# Connectors_2.net
KiCad netlist of a schematic drawn in Altium Designer
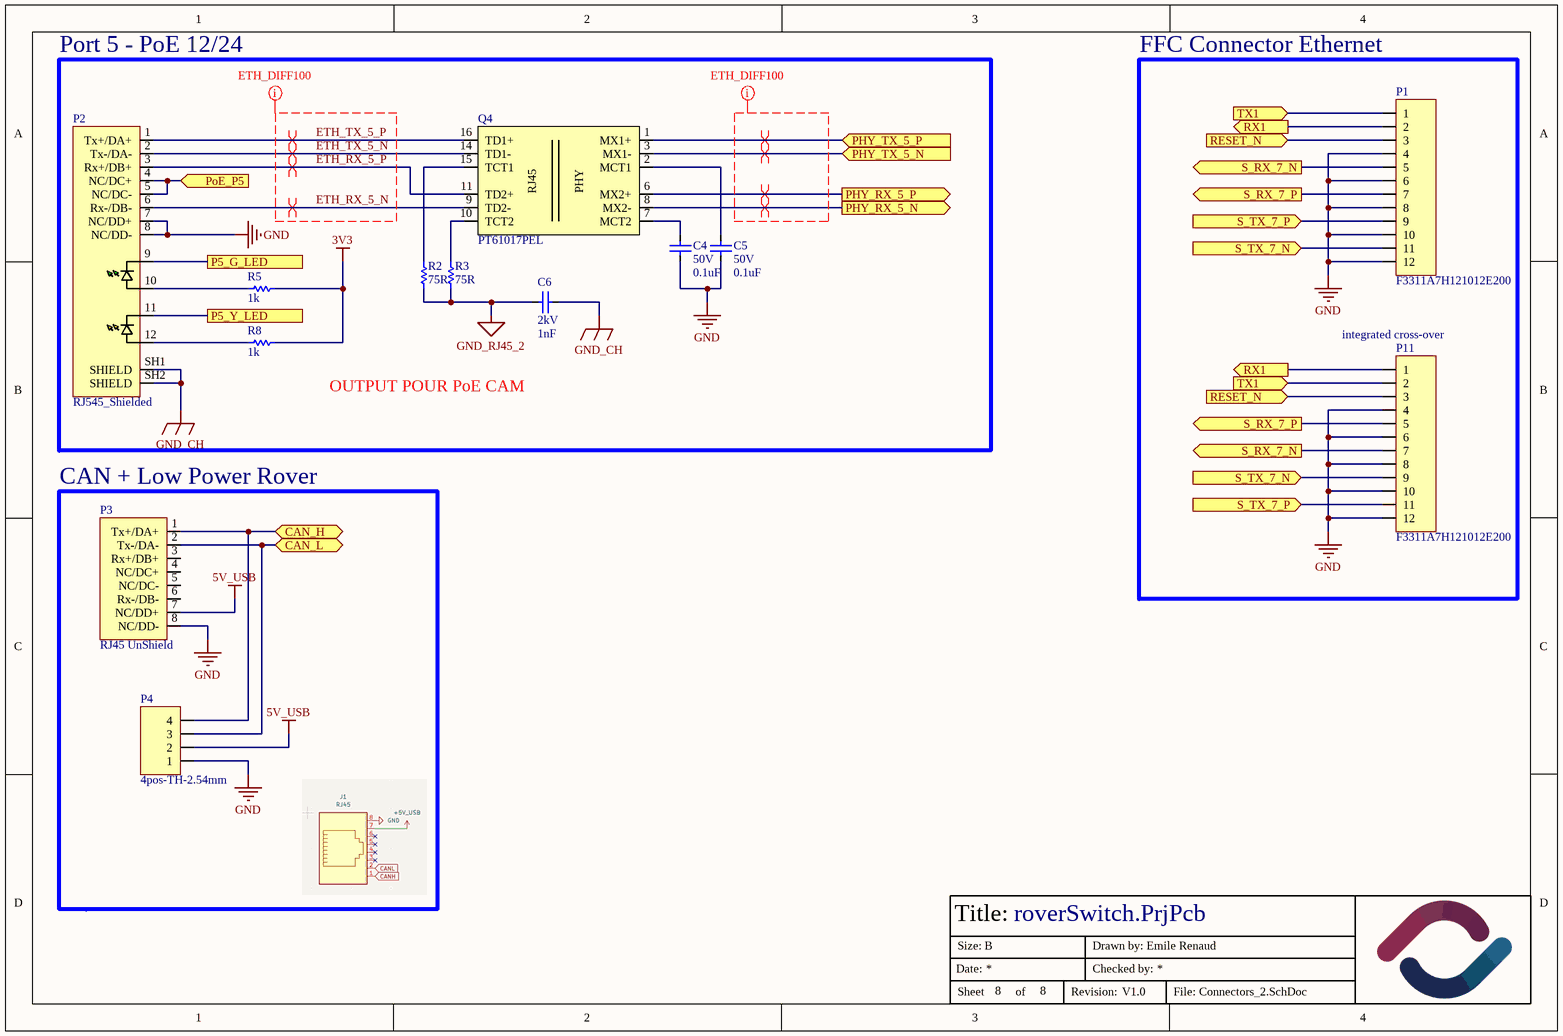
[diagram p0: Connectors_2.SchDoc]

(export (version "E")
  (design (tool "Eeschema 10.0.6"))
  (components
    (comp (ref "C4")
      (value "0.1uF")
      (footprint "CAPACITOR-0603")
      (description "Capacitor-0603-0.1uF-50V-X7R")
      (fields (field (name "VOLT") "50V"))
      (libsource (lib "Capacitors") (part "Capacitor-0603-0.1uF-50V-X7R"))
    )
    (comp (ref "C5")
      (value "0.1uF")
      (footprint "CAPACITOR-0603")
      (description "Capacitor-0603-0.1uF-50V-X7R")
      (fields (field (name "VOLT") "50V"))
      (libsource (lib "Capacitors") (part "Capacitor-0603-0.1uF-50V-X7R"))
    )
    (comp (ref "C6")
      (value "1nF")
      (footprint "CAPACITOR-1206")
      (description "Capacitor-1206-1nF-2kV-X7R")
      (fields (field (name "VOLT") "2kV"))
      (libsource (lib "Capacitors") (part "Capacitor-1206-1nF-2kV-X7R"))
    )
    (comp (ref "P1")
      (value "F3311A7H121012E200")
      (footprint "AMPHENOL_F3311A7H121012E200")
      (description "CONN FFC FPC 12POS 0.5MM R/A")
      (libsource (lib "FFC_connector") (part "FFC-12P-0.5MM-R/A"))
    )
    (comp (ref "P2")
      (value "RJ545_Shielded")
      (footprint "ADAMTECH_MTJ-88ARX1-FSM-LG")
      (description "Jack Modular Connector 8p8c (RJ45, Ethernet) 90° Angle (Right) Shielded with LEDs")
      (libsource (lib "PC-connector") (part "RJ545_Shielded"))
    )
    (comp (ref "P3")
      (value "RJ45 UnShield")
      (footprint "AMPHENOL_54602-908LF")
      (description "Jack Modular Connector 8p8c (RJ45, Ethernet) 90° Angle (Right) Unshielded Cat3")
      (libsource (lib "PC-connector") (part "RJ545"))
    )
    (comp (ref "P4")
      (value "4pos-TH-2.54mm")
      (footprint "HDR1X4")
      (description "4pos TH 2.54mm Header")
      (libsource (lib "Header") (part "4pos-TH-2.54mm"))
    )
    (comp (ref "P11")
      (value "F3311A7H121012E200")
      (footprint "AMPHENOL_F3311A7H121012E200")
      (description "CONN FFC FPC 12POS 0.5MM R/A")
      (libsource (lib "FFC_connector") (part "FFC-12P-0.5MM-R/A"))
    )
    (comp (ref "Q4")
      (value "PT61017PEL")
      (footprint "SOIC_PT61017PEL")
      (description "350µH LAN 10/100 Base-T Pulse Transformer 1CT:1CT Surface Mount")
      (libsource (lib "Transformers-Magnetics") (part "PT61017PEL"))
    )
    (comp (ref "R2")
      (value "75R")
      (footprint "Resistor-0603")
      (description "Resistor0603-75R")
      (fields (field (name "Comment") "SMT resistor"))
      (libsource (lib "Resistors") (part "Resistor-0603-75R"))
    )
    (comp (ref "R3")
      (value "75R")
      (footprint "Resistor-0603")
      (description "Resistor0603-75R")
      (fields (field (name "Comment") "SMT resistor"))
      (libsource (lib "Resistors") (part "Resistor-0603-75R"))
    )
    (comp (ref "R5")
      (value "1k")
      (footprint "Resistor-0603")
      (description "Resistor0603-1k")
      (fields (field (name "Comment") "SMT resistor"))
      (libsource (lib "Resistors") (part "Resistor-0603-1k"))
    )
    (comp (ref "R8")
      (value "1k")
      (footprint "Resistor-0603")
      (description "Resistor0603-1k")
      (fields (field (name "Comment") "SMT resistor"))
      (libsource (lib "Resistors") (part "Resistor-0603-1k"))
    )
  )
  (nets
    (net (code "1") (name "/CAN_H") (class "Default")
      (node (ref "P3") (pin "1") (pinfunction "Tx+/DA+_1") (pintype "passive"))
      (node (ref "P4") (pin "4") (pinfunction "4_4") (pintype "passive"))
    )
    (net (code "2") (name "/CAN_L") (class "Default")
      (node (ref "P3") (pin "2") (pinfunction "Tx-/DA-_2") (pintype "passive"))
      (node (ref "P4") (pin "3") (pinfunction "3_3") (pintype "passive"))
    )
    (net (code "3") (name "/ETH_RX_5_N") (class "Default")
      (node (ref "P2") (pin "6") (pinfunction "Rx-/DB-_6") (pintype "passive"))
      (node (ref "Q4") (pin "9") (pinfunction "TD2-_9") (pintype "passive"))
    )
    (net (code "4") (name "/ETH_RX_5_P") (class "Default")
      (node (ref "P2") (pin "3") (pinfunction "Rx+/DB+_3") (pintype "passive"))
      (node (ref "Q4") (pin "11") (pinfunction "TD2+_11") (pintype "passive"))
    )
    (net (code "5") (name "/ETH_TX_5_N") (class "Default")
      (node (ref "P2") (pin "2") (pinfunction "Tx-/DA-_2") (pintype "passive"))
      (node (ref "Q4") (pin "14") (pinfunction "TD1-_14") (pintype "passive"))
    )
    (net (code "6") (name "/ETH_TX_5_P") (class "Default")
      (node (ref "P2") (pin "1") (pinfunction "Tx+/DA+_1") (pintype "passive"))
      (node (ref "Q4") (pin "16") (pinfunction "TD1+_16") (pintype "passive"))
    )
    (net (code "7") (name "/P5_G_LED") (class "Default")
      (node (ref "P2") (pin "9") (pinfunction "9_9") (pintype "passive"))
    )
    (net (code "8") (name "/P5_Y_LED") (class "Default")
      (node (ref "P2") (pin "11") (pinfunction "11_11") (pintype "passive"))
    )
    (net (code "9") (name "/PHY_RX_5_N") (class "Default")
      (node (ref "Q4") (pin "8") (pinfunction "MX2-_8") (pintype "passive"))
    )
    (net (code "10") (name "/PHY_RX_5_P") (class "Default")
      (node (ref "Q4") (pin "6") (pinfunction "MX2+_6") (pintype "passive"))
    )
    (net (code "11") (name "/PHY_TX_5_N") (class "Default")
      (node (ref "Q4") (pin "3") (pinfunction "MX1-_3") (pintype "passive"))
    )
    (net (code "12") (name "/PHY_TX_5_P") (class "Default")
      (node (ref "Q4") (pin "1") (pinfunction "MX1+_1") (pintype "passive"))
    )
    (net (code "13") (name "/PoE_P5") (class "Default")
      (node (ref "P2") (pin "4") (pinfunction "NC/DC+_4") (pintype "passive"))
      (node (ref "P2") (pin "5") (pinfunction "NC/DC-_5") (pintype "passive"))
    )
    (net (code "14") (name "/RESET_N") (class "Default")
      (node (ref "P1") (pin "3") (pinfunction "3_3") (pintype "passive"))
      (node (ref "P11") (pin "3") (pinfunction "3_3") (pintype "passive"))
    )
    (net (code "15") (name "/RX1") (class "Default")
      (node (ref "P1") (pin "2") (pinfunction "2_2") (pintype "passive"))
      (node (ref "P11") (pin "1") (pinfunction "1_1") (pintype "passive"))
    )
    (net (code "16") (name "/S_RX_7_N") (class "Default")
      (node (ref "P1") (pin "5") (pinfunction "5_5") (pintype "passive"))
      (node (ref "P11") (pin "7") (pinfunction "7_7") (pintype "passive"))
    )
    (net (code "17") (name "/S_RX_7_P") (class "Default")
      (node (ref "P1") (pin "7") (pinfunction "7_7") (pintype "passive"))
      (node (ref "P11") (pin "5") (pinfunction "5_5") (pintype "passive"))
    )
    (net (code "18") (name "/S_TX_7_N") (class "Default")
      (node (ref "P1") (pin "11") (pinfunction "11_11") (pintype "passive"))
      (node (ref "P11") (pin "9") (pinfunction "9_9") (pintype "passive"))
    )
    (net (code "19") (name "/S_TX_7_P") (class "Default")
      (node (ref "P1") (pin "9") (pinfunction "9_9") (pintype "passive"))
      (node (ref "P11") (pin "11") (pinfunction "11_11") (pintype "passive"))
    )
    (net (code "20") (name "/TX1") (class "Default")
      (node (ref "P1") (pin "1") (pinfunction "1_1") (pintype "passive"))
      (node (ref "P11") (pin "2") (pinfunction "2_2") (pintype "passive"))
    )
    (net (code "21") (name "3V3") (class "Default")
      (node (ref "R5") (pin "1") (pinfunction "1_1") (pintype "passive"))
      (node (ref "R8") (pin "1") (pinfunction "1_1") (pintype "passive"))
    )
    (net (code "22") (name "5V_USB") (class "Default")
      (node (ref "P3") (pin "7") (pinfunction "NC/DD+_7") (pintype "passive"))
      (node (ref "P4") (pin "2") (pinfunction "2_2") (pintype "passive"))
    )
    (net (code "23") (name "GND") (class "Default")
      (node (ref "C4") (pin "1") (pinfunction "1_1") (pintype "passive"))
      (node (ref "C5") (pin "1") (pinfunction "1_1") (pintype "passive"))
      (node (ref "P1") (pin "10") (pinfunction "10_10") (pintype "passive"))
      (node (ref "P1") (pin "12") (pinfunction "12_12") (pintype "passive"))
      (node (ref "P1") (pin "4") (pinfunction "4_4") (pintype "passive"))
      (node (ref "P1") (pin "6") (pinfunction "6_6") (pintype "passive"))
      (node (ref "P1") (pin "8") (pinfunction "8_8") (pintype "passive"))
      (node (ref "P11") (pin "10") (pinfunction "10_10") (pintype "passive"))
      (node (ref "P11") (pin "12") (pinfunction "12_12") (pintype "passive"))
      (node (ref "P11") (pin "4") (pinfunction "4_4") (pintype "passive"))
      (node (ref "P11") (pin "6") (pinfunction "6_6") (pintype "passive"))
      (node (ref "P11") (pin "8") (pinfunction "8_8") (pintype "passive"))
      (node (ref "P2") (pin "7") (pinfunction "NC/DD+_7") (pintype "passive"))
      (node (ref "P2") (pin "8") (pinfunction "NC/DD-_8") (pintype "passive"))
      (node (ref "P3") (pin "8") (pinfunction "NC/DD-_8") (pintype "passive"))
      (node (ref "P4") (pin "1") (pinfunction "1_1") (pintype "passive"))
    )
    (net (code "24") (name "GND_CH") (class "Default")
      (node (ref "C6") (pin "2") (pinfunction "2_2") (pintype "passive"))
      (node (ref "P2") (pin "SH1") (pinfunction "SHIELD_SH1") (pintype "passive"))
      (node (ref "P2") (pin "SH2") (pinfunction "SHIELD_SH2") (pintype "passive"))
    )
    (net (code "25") (name "GND_RJ45_2") (class "Default")
      (node (ref "C6") (pin "1") (pinfunction "1_1") (pintype "passive"))
      (node (ref "R2") (pin "1") (pinfunction "1_1") (pintype "passive"))
      (node (ref "R3") (pin "1") (pinfunction "1_1") (pintype "passive"))
    )
    (net (code "26") (name "Net-(P2-Pad10)") (class "Default")
      (node (ref "P2") (pin "10") (pinfunction "10_10") (pintype "passive"))
      (node (ref "R5") (pin "2") (pinfunction "2_2") (pintype "passive"))
    )
    (net (code "27") (name "Net-(P2-Pad12)") (class "Default")
      (node (ref "P2") (pin "12") (pinfunction "12_12") (pintype "passive"))
      (node (ref "R8") (pin "2") (pinfunction "2_2") (pintype "passive"))
    )
    (net (code "28") (name "Net-(Q4-MCT1)") (class "Default")
      (node (ref "C5") (pin "2") (pinfunction "2_2") (pintype "passive"))
      (node (ref "Q4") (pin "2") (pinfunction "MCT1_2") (pintype "passive"))
    )
    (net (code "29") (name "Net-(Q4-MCT2)") (class "Default")
      (node (ref "C4") (pin "2") (pinfunction "2_2") (pintype "passive"))
      (node (ref "Q4") (pin "7") (pinfunction "MCT2_7") (pintype "passive"))
    )
    (net (code "30") (name "Net-(Q4-TCT1)") (class "Default")
      (node (ref "Q4") (pin "15") (pinfunction "TCT1_15") (pintype "passive"))
      (node (ref "R2") (pin "2") (pinfunction "2_2") (pintype "passive"))
    )
    (net (code "31") (name "Net-(Q4-TCT2)") (class "Default")
      (node (ref "Q4") (pin "10") (pinfunction "TCT2_10") (pintype "passive"))
      (node (ref "R3") (pin "2") (pinfunction "2_2") (pintype "passive"))
    )
    (net (code "32") (name "unconnected-(P3-NC{slash}DC+-Pad4)") (class "Default")
      (node (ref "P3") (pin "4") (pinfunction "NC/DC+_4") (pintype "passive"))
    )
    (net (code "33") (name "unconnected-(P3-NC{slash}DC--Pad5)") (class "Default")
      (node (ref "P3") (pin "5") (pinfunction "NC/DC-_5") (pintype "passive"))
    )
    (net (code "34") (name "unconnected-(P3-Rx+{slash}DB+-Pad3)") (class "Default")
      (node (ref "P3") (pin "3") (pinfunction "Rx+/DB+_3") (pintype "passive"))
    )
    (net (code "35") (name "unconnected-(P3-Rx-{slash}DB--Pad6)") (class "Default")
      (node (ref "P3") (pin "6") (pinfunction "Rx-/DB-_6") (pintype "passive"))
    )
  )
)
